# Telemetry_Transceiver_Board.net
KiCad netlist of a schematic drawn in EAGLE
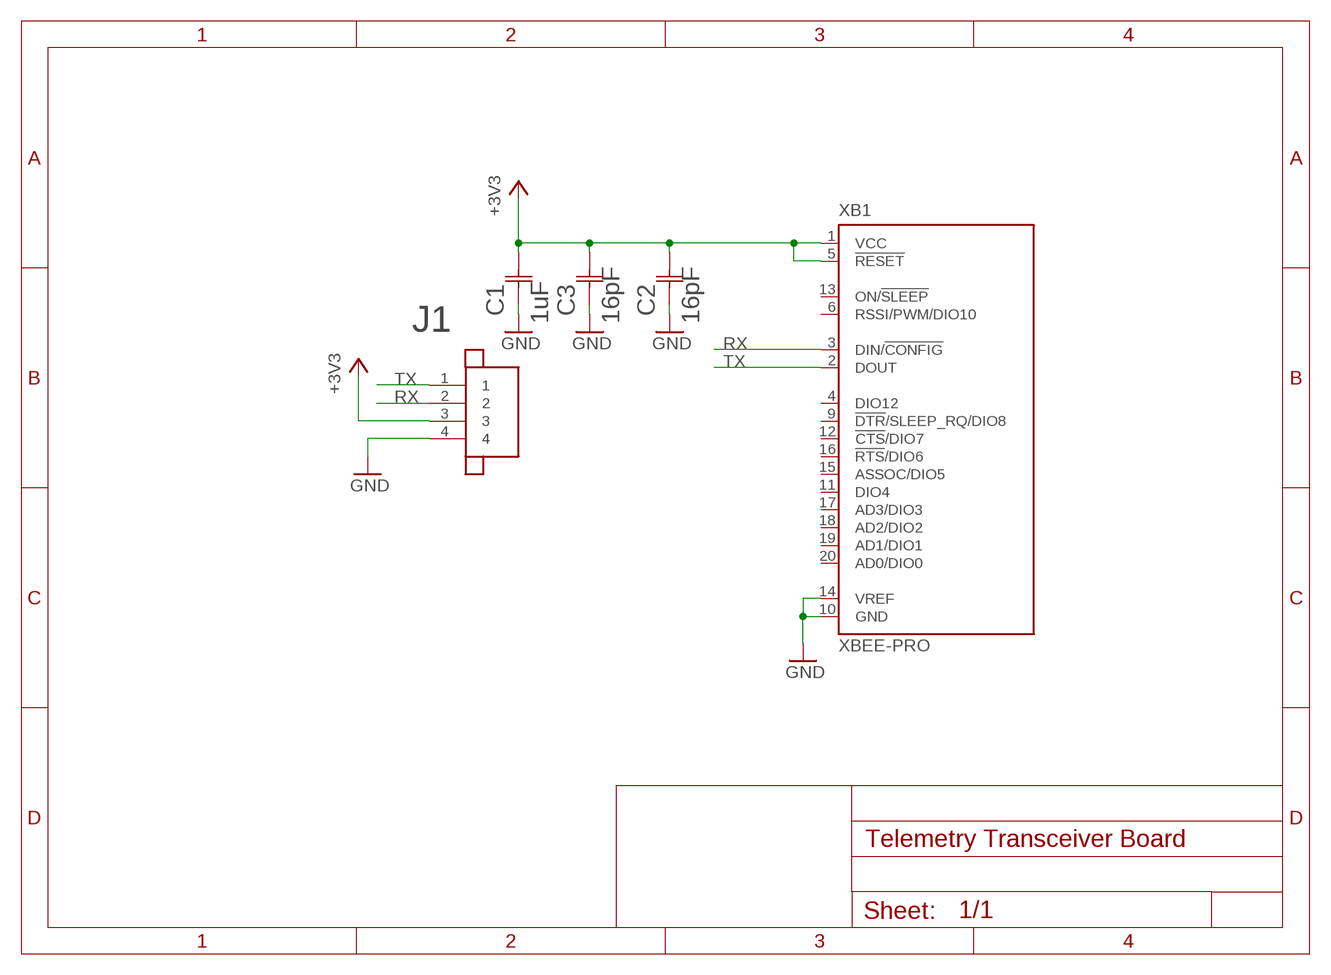
[diagram p0: schematic, sheet 1]

(export (version "E")
  (design (tool "Eeschema 10.0.6"))
  (components
    (comp (ref "C1")
      (value "1uF")
      (footprint "eagle-import:YAG_CC0805")
      (fields
        (field (name "MANUFACTURER_PART_NUMBER") "CC0805KKX7R7BB105")
        (field (name "COPYRIGHT") "Copyright C 2015 Accelerated Designs. All rights reserved")
      )
      (libsource (lib "eagle-import") (part "CC0805KKX7R7BB105"))
    )
    (comp (ref "C2")
      (value "16pF")
      (footprint "eagle-import:G-155-M")
      (fields (field (name "MANUFACTURER_PART_NUMBER") "GRM1555C1H160JA01D"))
      (libsource (lib "eagle-import") (part "GRM1555C1H160JA01DG-155-M"))
    )
    (comp (ref "C3")
      (value "16pF")
      (footprint "eagle-import:G-155-M")
      (fields (field (name "MANUFACTURER_PART_NUMBER") "GRM1555C1H160JA01D"))
      (libsource (lib "eagle-import") (part "GRM1555C1H160JA01DG-155-M"))
    )
    (comp (ref "J1")
      (value "JST_SH_4POS")
      (footprint "eagle-import:JST_SH_4POS")
      (libsource (lib "eagle-import") (part "JST_SH_4POS"))
    )
    (comp (ref "XB1")
      (value "XBEE-PRO")
      (footprint "eagle-import:XBEE-PRO")
      (fields (field (name "MPN") "XBP24-AWI-001"))
      (libsource (lib "eagle-import") (part "XBEE-PRO"))
    )
  )
  (nets
    (net (code "1") (name "+3V3") (class "Default")
      (node (ref "C1") (pin "2") (pinfunction "22_2") (pintype "passive"))
      (node (ref "C2") (pin "2") (pinfunction "22_2") (pintype "passive"))
      (node (ref "C3") (pin "2") (pinfunction "22_2") (pintype "passive"))
      (node (ref "J1") (pin "3") (pinfunction "3_3") (pintype "bidirectional"))
      (node (ref "XB1") (pin "1") (pinfunction "VCC_1") (pintype "power_in"))
      (node (ref "XB1") (pin "5") (pinfunction "~{RESET}_5") (pintype "input"))
    )
    (net (code "2") (name "/RX") (class "Default")
      (node (ref "J1") (pin "2") (pinfunction "2_2") (pintype "bidirectional"))
      (node (ref "XB1") (pin "3") (pinfunction "DIN/~{CONFIG}_3") (pintype "input"))
    )
    (net (code "3") (name "/TX") (class "Default")
      (node (ref "J1") (pin "1") (pinfunction "1_1") (pintype "bidirectional"))
      (node (ref "XB1") (pin "2") (pinfunction "DOUT_2") (pintype "output"))
    )
    (net (code "4") (name "GND") (class "Default")
      (node (ref "C1") (pin "1") (pinfunction "11_1") (pintype "passive"))
      (node (ref "C2") (pin "1") (pinfunction "11_1") (pintype "passive"))
      (node (ref "C3") (pin "1") (pinfunction "11_1") (pintype "passive"))
      (node (ref "J1") (pin "4") (pinfunction "4_4") (pintype "bidirectional"))
      (node (ref "XB1") (pin "10") (pinfunction "GND_10") (pintype "power_in"))
      (node (ref "XB1") (pin "14") (pinfunction "VREF_14") (pintype "input"))
    )
    (net (code "5") (name "unconnected-(XB1-AD0{slash}DIO0-Pad20)") (class "Default")
      (node (ref "XB1") (pin "20") (pinfunction "AD0/DIO0_20") (pintype "bidirectional"))
    )
    (net (code "6") (name "unconnected-(XB1-AD1{slash}DIO1-Pad19)") (class "Default")
      (node (ref "XB1") (pin "19") (pinfunction "AD1/DIO1_19") (pintype "bidirectional"))
    )
    (net (code "7") (name "unconnected-(XB1-AD2{slash}DIO2-Pad18)") (class "Default")
      (node (ref "XB1") (pin "18") (pinfunction "AD2/DIO2_18") (pintype "bidirectional"))
    )
    (net (code "8") (name "unconnected-(XB1-AD3{slash}DIO3-Pad17)") (class "Default")
      (node (ref "XB1") (pin "17") (pinfunction "AD3/DIO3_17") (pintype "bidirectional"))
    )
    (net (code "9") (name "unconnected-(XB1-ASSOC{slash}DIO5-Pad15)") (class "Default")
      (node (ref "XB1") (pin "15") (pinfunction "ASSOC/DIO5_15") (pintype "bidirectional"))
    )
    (net (code "10") (name "unconnected-(XB1-DIO4-Pad11)") (class "Default")
      (node (ref "XB1") (pin "11") (pinfunction "DIO4_11") (pintype "bidirectional"))
    )
    (net (code "11") (name "unconnected-(XB1-DIO12-Pad4)") (class "Default")
      (node (ref "XB1") (pin "4") (pinfunction "DIO12_4") (pintype "bidirectional"))
    )
    (net (code "12") (name "unconnected-(XB1-ON{slash}~{SLEEP}-Pad13)") (class "Default")
      (node (ref "XB1") (pin "13") (pinfunction "ON/~{SLEEP}_13") (pintype "output"))
    )
    (net (code "13") (name "unconnected-(XB1-RSSI{slash}PWM{slash}DIO10-Pad6)") (class "Default")
      (node (ref "XB1") (pin "6") (pinfunction "RSSI/PWM/DIO10_6") (pintype "output"))
    )
    (net (code "14") (name "unconnected-(XB1-~{CTS}{slash}DIO7-Pad12)") (class "Default")
      (node (ref "XB1") (pin "12") (pinfunction "~{CTS}/DIO7_12") (pintype "bidirectional"))
    )
    (net (code "15") (name "unconnected-(XB1-~{DTR}{slash}SLEEP_RQ{slash}DIO8-Pad9)") (class "Default")
      (node (ref "XB1") (pin "9") (pinfunction "~{DTR}/SLEEP_RQ/DIO8_9") (pintype "bidirectional"))
    )
    (net (code "16") (name "unconnected-(XB1-~{RTS}{slash}DIO6-Pad16)") (class "Default")
      (node (ref "XB1") (pin "16") (pinfunction "~{RTS}/DIO6_16") (pintype "bidirectional"))
    )
  )
)
